# tusb8041_hub_test.net
KiCad netlist of a schematic drawn in EAGLE
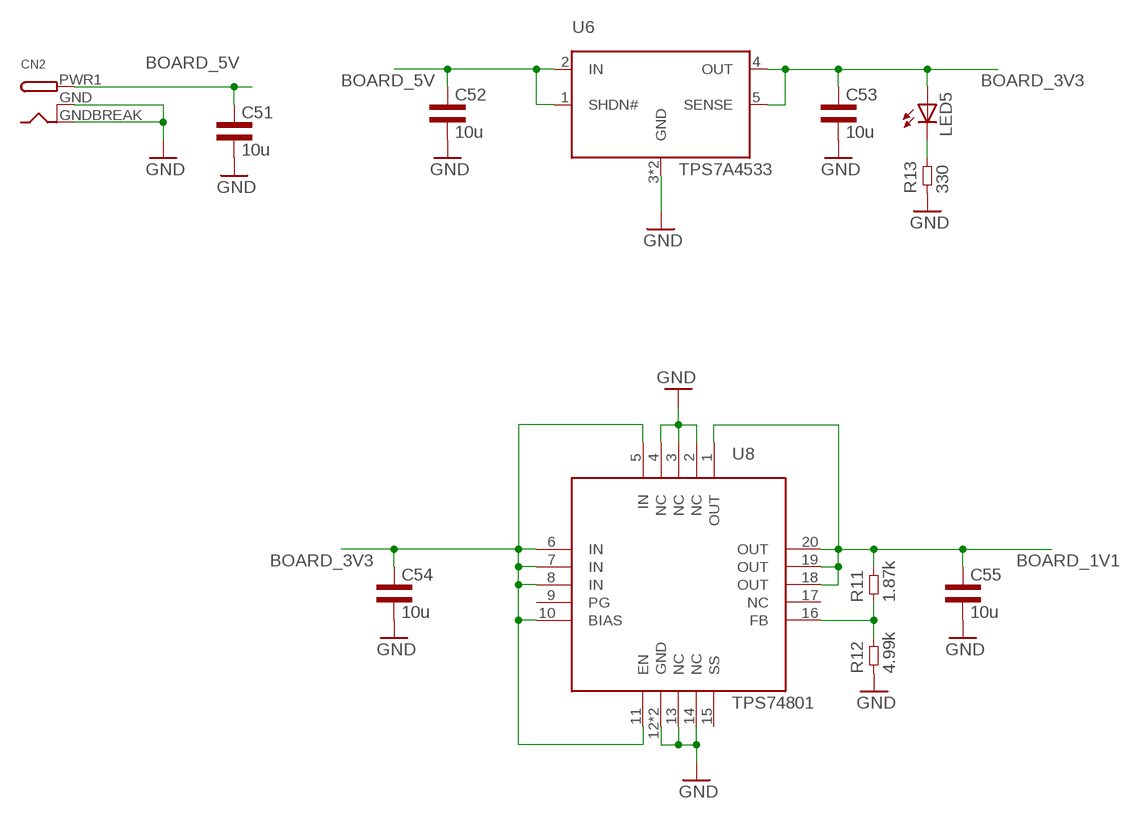
[diagram p0: schematic, sheet 1]
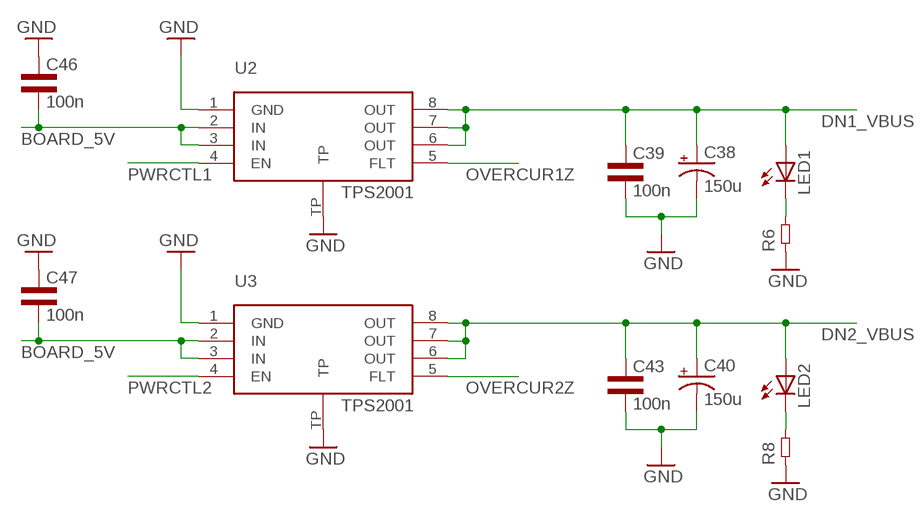
[diagram p1: schematic, sheet 2]
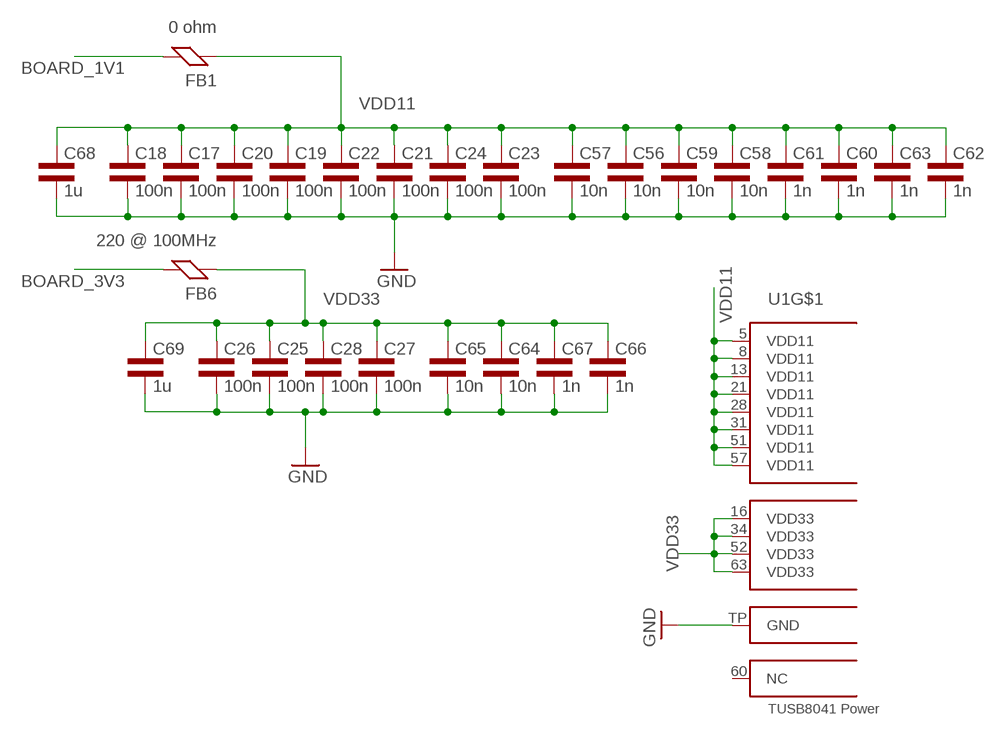
[diagram p2: schematic, sheet 3]
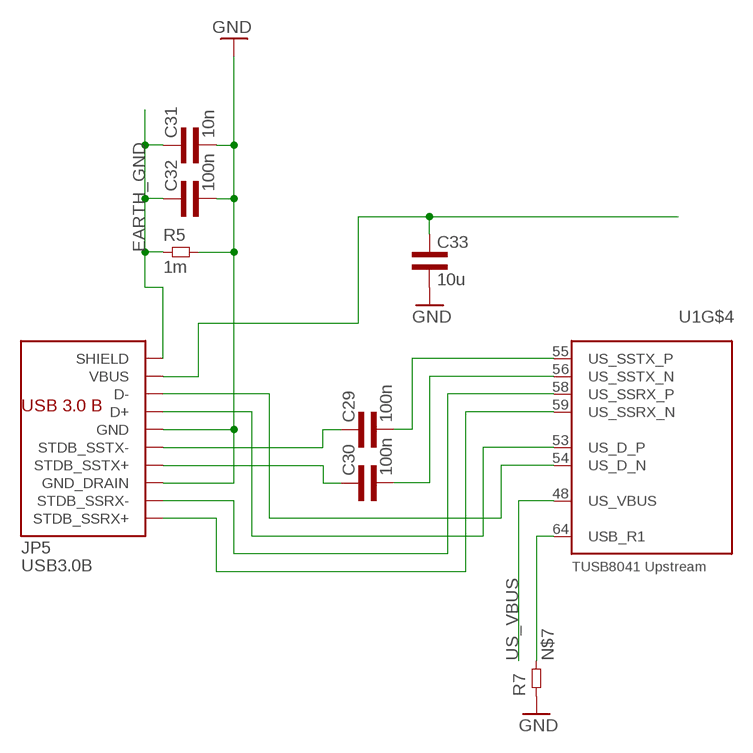
[diagram p3: schematic, sheet 4]
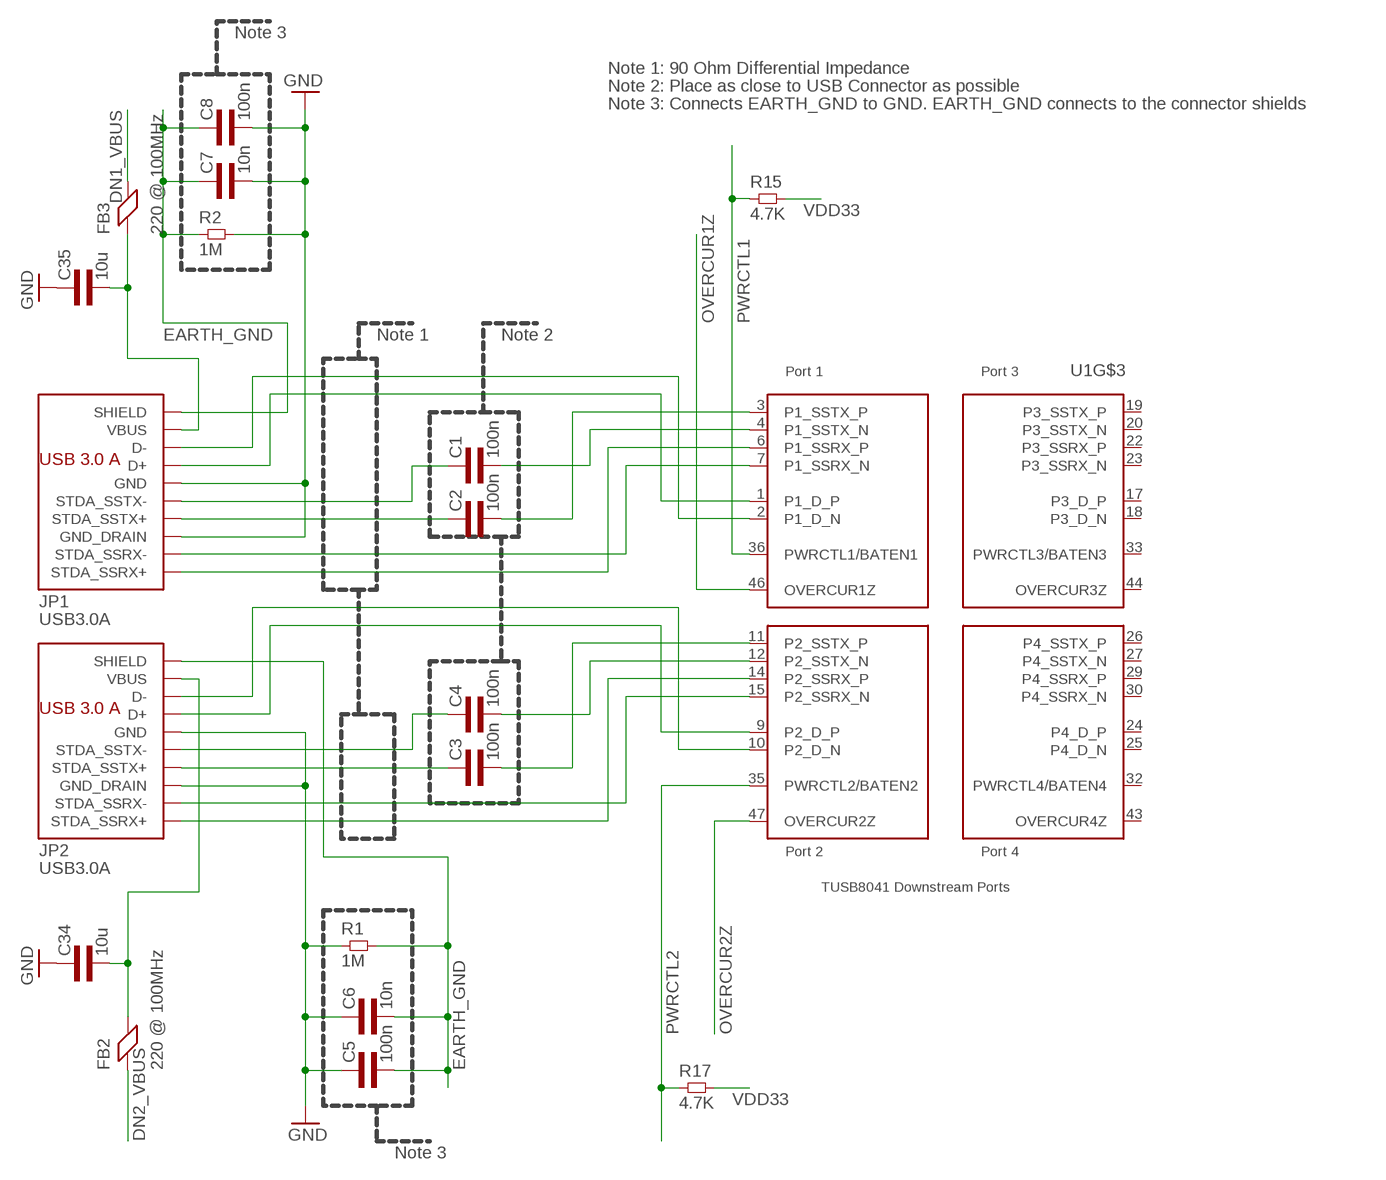
[diagram p4: schematic, sheet 5]
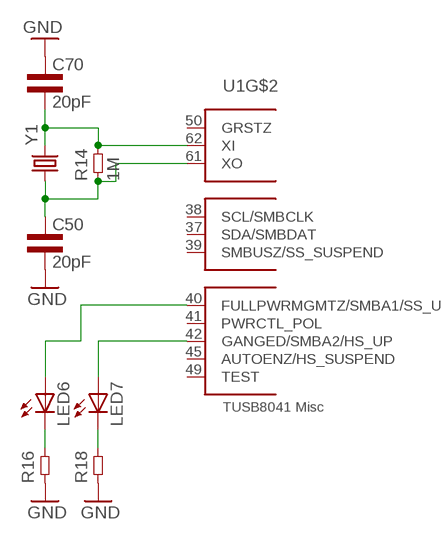
[diagram p5: schematic, sheet 6]

(export (version "E")
  (design (tool "Eeschema 10.0.6"))
  (components
    (comp (ref "C29")
      (value "100n")
      (footprint "eagle-import:0402L3")
      (libsource (lib "eagle-import") (part "CAP0402L3"))
    )
    (comp (ref "C30")
      (value "100n")
      (footprint "eagle-import:0402L3")
      (libsource (lib "eagle-import") (part "CAP0402L3"))
    )
    (comp (ref "C31")
      (value "10n")
      (footprint "eagle-import:0603L3")
      (libsource (lib "eagle-import") (part "CAP0603L3"))
    )
    (comp (ref "C32")
      (value "100n")
      (footprint "eagle-import:0603L3")
      (libsource (lib "eagle-import") (part "CAP0603L3"))
    )
    (comp (ref "C33")
      (value "10u")
      (footprint "eagle-import:1206L3")
      (libsource (lib "eagle-import") (part "CAP1206L3"))
    )
    (comp (ref "JP5")
      (value "USB3.0B")
      (footprint "eagle-import:AMPHENOLUSB3.0B")
      (libsource (lib "eagle-import") (part "USB3.0B"))
    )
    (comp (ref "R5")
      (value "1m")
      (footprint "eagle-import:0603L3")
      (libsource (lib "eagle-import") (part "RES0603L3"))
    )
    (comp (ref "R7")
      (value "RES0402L3")
      (footprint "eagle-import:0402L3")
      (libsource (lib "eagle-import") (part "RES0402L3"))
    )
    (comp (ref "U1")
      (value "TUSB8041")
      (footprint "eagle-import:VQFN64")
      (libsource (lib "eagle-import") (part "TUSB8041"))
    )
    (comp (ref "C50")
      (value "20pF")
      (footprint "eagle-import:0402L3")
      (libsource (lib "eagle-import") (part "CAP0402L3"))
    )
    (comp (ref "C70")
      (value "20pF")
      (footprint "eagle-import:0402L3")
      (libsource (lib "eagle-import") (part "CAP0402L3"))
    )
    (comp (ref "LED6")
      (value "LEDCHIPLED_0603")
      (footprint "eagle-import:CHIPLED_0603")
      (libsource (lib "eagle-import") (part "LEDCHIPLED_0603"))
    )
    (comp (ref "LED7")
      (value "LEDCHIPLED_0603")
      (footprint "eagle-import:CHIPLED_0603")
      (libsource (lib "eagle-import") (part "LEDCHIPLED_0603"))
    )
    (comp (ref "R14")
      (value "1M")
      (footprint "eagle-import:0402L3")
      (libsource (lib "eagle-import") (part "RES0402L3"))
    )
    (comp (ref "R16")
      (value "RES0402L3")
      (footprint "eagle-import:0402L3")
      (libsource (lib "eagle-import") (part "RES0402L3"))
    )
    (comp (ref "R18")
      (value "RES0402L3")
      (footprint "eagle-import:0402L3")
      (libsource (lib "eagle-import") (part "RES0402L3"))
    )
    (comp (ref "Y1")
      (value "CRYSTALHC49US")
      (footprint "eagle-import:HC49US")
      (libsource (lib "eagle-import") (part "CRYSTALHC49US"))
    )
    (comp (ref "C17")
      (value "100n")
      (footprint "eagle-import:0402L3")
      (libsource (lib "eagle-import") (part "CAP0402L3"))
    )
    (comp (ref "C18")
      (value "100n")
      (footprint "eagle-import:0402L3")
      (libsource (lib "eagle-import") (part "CAP0402L3"))
    )
    (comp (ref "C19")
      (value "100n")
      (footprint "eagle-import:0402L3")
      (libsource (lib "eagle-import") (part "CAP0402L3"))
    )
    (comp (ref "C20")
      (value "100n")
      (footprint "eagle-import:0402L3")
      (libsource (lib "eagle-import") (part "CAP0402L3"))
    )
    (comp (ref "C21")
      (value "100n")
      (footprint "eagle-import:0402L3")
      (libsource (lib "eagle-import") (part "CAP0402L3"))
    )
    (comp (ref "C22")
      (value "100n")
      (footprint "eagle-import:0402L3")
      (libsource (lib "eagle-import") (part "CAP0402L3"))
    )
    (comp (ref "C23")
      (value "100n")
      (footprint "eagle-import:0402L3")
      (libsource (lib "eagle-import") (part "CAP0402L3"))
    )
    (comp (ref "C24")
      (value "100n")
      (footprint "eagle-import:0402L3")
      (libsource (lib "eagle-import") (part "CAP0402L3"))
    )
    (comp (ref "C25")
      (value "100n")
      (footprint "eagle-import:0402L3")
      (libsource (lib "eagle-import") (part "CAP0402L3"))
    )
    (comp (ref "C26")
      (value "100n")
      (footprint "eagle-import:0402L3")
      (libsource (lib "eagle-import") (part "CAP0402L3"))
    )
    (comp (ref "C27")
      (value "100n")
      (footprint "eagle-import:0402L3")
      (libsource (lib "eagle-import") (part "CAP0402L3"))
    )
    (comp (ref "C28")
      (value "100n")
      (footprint "eagle-import:0402L3")
      (libsource (lib "eagle-import") (part "CAP0402L3"))
    )
    (comp (ref "C56")
      (value "10n")
      (footprint "eagle-import:0402L3")
      (libsource (lib "eagle-import") (part "CAP0402L3"))
    )
    (comp (ref "C57")
      (value "10n")
      (footprint "eagle-import:0402L3")
      (libsource (lib "eagle-import") (part "CAP0402L3"))
    )
    (comp (ref "C58")
      (value "10n")
      (footprint "eagle-import:0402L3")
      (libsource (lib "eagle-import") (part "CAP0402L3"))
    )
    (comp (ref "C59")
      (value "10n")
      (footprint "eagle-import:0402L3")
      (libsource (lib "eagle-import") (part "CAP0402L3"))
    )
    (comp (ref "C60")
      (value "1n")
      (footprint "eagle-import:0402L3")
      (libsource (lib "eagle-import") (part "CAP0402L3"))
    )
    (comp (ref "C61")
      (value "1n")
      (footprint "eagle-import:0402L3")
      (libsource (lib "eagle-import") (part "CAP0402L3"))
    )
    (comp (ref "C62")
      (value "1n")
      (footprint "eagle-import:0402L3")
      (libsource (lib "eagle-import") (part "CAP0402L3"))
    )
    (comp (ref "C63")
      (value "1n")
      (footprint "eagle-import:0402L3")
      (libsource (lib "eagle-import") (part "CAP0402L3"))
    )
    (comp (ref "C64")
      (value "10n")
      (footprint "eagle-import:0402L3")
      (libsource (lib "eagle-import") (part "CAP0402L3"))
    )
    (comp (ref "C65")
      (value "10n")
      (footprint "eagle-import:0402L3")
      (libsource (lib "eagle-import") (part "CAP0402L3"))
    )
    (comp (ref "C66")
      (value "1n")
      (footprint "eagle-import:0402L3")
      (libsource (lib "eagle-import") (part "CAP0402L3"))
    )
    (comp (ref "C67")
      (value "1n")
      (footprint "eagle-import:0402L3")
      (libsource (lib "eagle-import") (part "CAP0402L3"))
    )
    (comp (ref "C68")
      (value "1u")
      (footprint "eagle-import:0805L3")
      (libsource (lib "eagle-import") (part "CAP0805L3"))
    )
    (comp (ref "C69")
      (value "1u")
      (footprint "eagle-import:0805L3")
      (libsource (lib "eagle-import") (part "CAP0805L3"))
    )
    (comp (ref "FB1")
      (value "0 ohm")
      (footprint "eagle-import:0603L3")
      (libsource (lib "eagle-import") (part "FERRITE0603L3"))
    )
    (comp (ref "FB6")
      (value "220 @ 100MHz")
      (footprint "eagle-import:0603L3")
      (libsource (lib "eagle-import") (part "FERRITE0603L3"))
    )
    (comp (ref "C1")
      (value "100n")
      (footprint "eagle-import:0402L3")
      (libsource (lib "eagle-import") (part "CAP0402L3"))
    )
    (comp (ref "C2")
      (value "100n")
      (footprint "eagle-import:0402L3")
      (libsource (lib "eagle-import") (part "CAP0402L3"))
    )
    (comp (ref "C3")
      (value "100n")
      (footprint "eagle-import:0402L3")
      (libsource (lib "eagle-import") (part "CAP0402L3"))
    )
    (comp (ref "C4")
      (value "100n")
      (footprint "eagle-import:0402L3")
      (libsource (lib "eagle-import") (part "CAP0402L3"))
    )
    (comp (ref "C5")
      (value "100n")
      (footprint "eagle-import:0603L3")
      (libsource (lib "eagle-import") (part "CAP0603L3"))
    )
    (comp (ref "C6")
      (value "10n")
      (footprint "eagle-import:0603L3")
      (libsource (lib "eagle-import") (part "CAP0603L3"))
    )
    (comp (ref "C7")
      (value "10n")
      (footprint "eagle-import:0603L3")
      (libsource (lib "eagle-import") (part "CAP0603L3"))
    )
    (comp (ref "C8")
      (value "100n")
      (footprint "eagle-import:0603L3")
      (libsource (lib "eagle-import") (part "CAP0603L3"))
    )
    (comp (ref "C34")
      (value "10u")
      (footprint "eagle-import:1206L3")
      (libsource (lib "eagle-import") (part "CAP1206L3"))
    )
    (comp (ref "C35")
      (value "10u")
      (footprint "eagle-import:1206L3")
      (libsource (lib "eagle-import") (part "CAP1206L3"))
    )
    (comp (ref "FB2")
      (value "220 @ 100MHz")
      (footprint "eagle-import:0603L1")
      (libsource (lib "eagle-import") (part "FERRITE0603L1"))
    )
    (comp (ref "FB3")
      (value "220 @ 100MHz")
      (footprint "eagle-import:0603L1")
      (libsource (lib "eagle-import") (part "FERRITE0603L1"))
    )
    (comp (ref "JP1")
      (value "USB3.0A")
      (footprint "eagle-import:AMPHENOLUSB3.0A")
      (libsource (lib "eagle-import") (part "USB3.0A"))
    )
    (comp (ref "JP2")
      (value "USB3.0A")
      (footprint "eagle-import:AMPHENOLUSB3.0A")
      (libsource (lib "eagle-import") (part "USB3.0A"))
    )
    (comp (ref "R1")
      (value "1M")
      (footprint "eagle-import:0603L3")
      (libsource (lib "eagle-import") (part "RES0603L3"))
    )
    (comp (ref "R2")
      (value "1M")
      (footprint "eagle-import:0603L3")
      (libsource (lib "eagle-import") (part "RES0603L3"))
    )
    (comp (ref "R15")
      (value "4.7K")
      (footprint "eagle-import:0402L3")
      (libsource (lib "eagle-import") (part "RES0402L3"))
    )
    (comp (ref "R17")
      (value "4.7K")
      (footprint "eagle-import:0402L3")
      (libsource (lib "eagle-import") (part "RES0402L3"))
    )
    (comp (ref "C51")
      (value "10u")
      (footprint "eagle-import:1206L3")
      (libsource (lib "eagle-import") (part "CAP1206L3"))
    )
    (comp (ref "C52")
      (value "10u")
      (footprint "eagle-import:1206L3")
      (libsource (lib "eagle-import") (part "CAP1206L3"))
    )
    (comp (ref "C53")
      (value "10u")
      (footprint "eagle-import:1206L3")
      (libsource (lib "eagle-import") (part "CAP1206L3"))
    )
    (comp (ref "C54")
      (value "10u")
      (footprint "eagle-import:1206L3")
      (libsource (lib "eagle-import") (part "CAP1206L3"))
    )
    (comp (ref "C55")
      (value "10u")
      (footprint "eagle-import:1206L3")
      (libsource (lib "eagle-import") (part "CAP1206L3"))
    )
    (comp (ref "CN2")
      (value "DCBARRELSMT")
      (footprint "eagle-import:DCJACK_2MM_SMT")
      (libsource (lib "eagle-import") (part "DCBARRELSMT"))
    )
    (comp (ref "LED5")
      (value "LEDCHIP-LED0603")
      (footprint "eagle-import:CHIP-LED0603")
      (libsource (lib "eagle-import") (part "LEDCHIP-LED0603"))
    )
    (comp (ref "R11")
      (value "1.87k")
      (footprint "eagle-import:0402L3")
      (libsource (lib "eagle-import") (part "RES0402L3"))
    )
    (comp (ref "R12")
      (value "4.99k")
      (footprint "eagle-import:0402L3")
      (libsource (lib "eagle-import") (part "RES0402L3"))
    )
    (comp (ref "R13")
      (value "330")
      (footprint "eagle-import:0603L3")
      (libsource (lib "eagle-import") (part "RES0603L3"))
    )
    (comp (ref "U6")
      (value "TPS7A4533")
      (footprint "eagle-import:R-PSFM-G5")
      (libsource (lib "eagle-import") (part "TPS7A4533"))
    )
    (comp (ref "U8")
      (value "TPS74801")
      (footprint "eagle-import:S-PVQFN-N20")
      (libsource (lib "eagle-import") (part "TPS74801"))
    )
    (comp (ref "C38")
      (value "150u")
      (footprint "eagle-import:CT7343")
      (libsource (lib "eagle-import") (part "CPOL-USCT7343"))
    )
    (comp (ref "C39")
      (value "100n")
      (footprint "eagle-import:0603L3")
      (libsource (lib "eagle-import") (part "CAP0603L3"))
    )
    (comp (ref "C40")
      (value "150u")
      (footprint "eagle-import:CT7343")
      (libsource (lib "eagle-import") (part "CPOL-USCT7343"))
    )
    (comp (ref "C43")
      (value "100n")
      (footprint "eagle-import:0603L3")
      (libsource (lib "eagle-import") (part "CAP0603L3"))
    )
    (comp (ref "C46")
      (value "100n")
      (footprint "eagle-import:0603L3")
      (libsource (lib "eagle-import") (part "CAP0603L3"))
    )
    (comp (ref "C47")
      (value "100n")
      (footprint "eagle-import:0603L3")
      (libsource (lib "eagle-import") (part "CAP0603L3"))
    )
    (comp (ref "LED1")
      (value "LEDCHIP-LED0603")
      (footprint "eagle-import:CHIP-LED0603")
      (libsource (lib "eagle-import") (part "LEDCHIP-LED0603"))
    )
    (comp (ref "LED2")
      (value "LEDCHIP-LED0603")
      (footprint "eagle-import:CHIP-LED0603")
      (libsource (lib "eagle-import") (part "LEDCHIP-LED0603"))
    )
    (comp (ref "R6")
      (value "RES0603L3")
      (footprint "eagle-import:0603L3")
      (libsource (lib "eagle-import") (part "RES0603L3"))
    )
    (comp (ref "R8")
      (value "RES0603L3")
      (footprint "eagle-import:0603L3")
      (libsource (lib "eagle-import") (part "RES0603L3"))
    )
    (comp (ref "U2")
      (value "TPS2001")
      (footprint "eagle-import:S-PDSO-G8")
      (libsource (lib "eagle-import") (part "TPS2001"))
    )
    (comp (ref "U3")
      (value "TPS2001")
      (footprint "eagle-import:S-PDSO-G8")
      (libsource (lib "eagle-import") (part "TPS2001"))
    )
  )
  (nets
    (net (code "1") (name "BOARD_1V1") (class "Default")
      (node (ref "C55") (pin "1") (pinfunction "1_1") (pintype "bidirectional"))
      (node (ref "FB1") (pin "P$2") (pinfunction "2_P$2") (pintype "bidirectional"))
      (node (ref "R11") (pin "P$2") (pinfunction "2_P$2") (pintype "bidirectional"))
      (node (ref "U8") (pin "1") (pinfunction "OUT_1") (pintype "bidirectional"))
      (node (ref "U8") (pin "18") (pinfunction "OUT_18") (pintype "bidirectional"))
      (node (ref "U8") (pin "19") (pinfunction "OUT_19") (pintype "bidirectional"))
      (node (ref "U8") (pin "20") (pinfunction "OUT_20") (pintype "bidirectional"))
    )
    (net (code "2") (name "BOARD_3V3") (class "Default")
      (node (ref "C53") (pin "1") (pinfunction "1_1") (pintype "bidirectional"))
      (node (ref "C54") (pin "1") (pinfunction "1_1") (pintype "bidirectional"))
      (node (ref "FB6") (pin "P$2") (pinfunction "2_P$2") (pintype "bidirectional"))
      (node (ref "LED5") (pin "A") (pinfunction "A_A") (pintype "passive"))
      (node (ref "U6") (pin "4") (pinfunction "OUT_4") (pintype "bidirectional"))
      (node (ref "U6") (pin "5") (pinfunction "SENSE_5") (pintype "bidirectional"))
      (node (ref "U8") (pin "10") (pinfunction "BIAS_10") (pintype "bidirectional"))
      (node (ref "U8") (pin "11") (pinfunction "EN_11") (pintype "bidirectional"))
      (node (ref "U8") (pin "5") (pinfunction "IN_5") (pintype "bidirectional"))
      (node (ref "U8") (pin "6") (pinfunction "IN_6") (pintype "bidirectional"))
      (node (ref "U8") (pin "7") (pinfunction "IN_7") (pintype "bidirectional"))
      (node (ref "U8") (pin "8") (pinfunction "IN_8") (pintype "bidirectional"))
    )
    (net (code "3") (name "BOARD_5V") (class "Default")
      (node (ref "C46") (pin "P$2") (pinfunction "2_P$2") (pintype "bidirectional"))
      (node (ref "C47") (pin "P$2") (pinfunction "2_P$2") (pintype "bidirectional"))
      (node (ref "C51") (pin "1") (pinfunction "1_1") (pintype "bidirectional"))
      (node (ref "C52") (pin "1") (pinfunction "1_1") (pintype "bidirectional"))
      (node (ref "CN2") (pin "PWR1") (pinfunction "PWR_PWR1") (pintype "power_in"))
      (node (ref "U2") (pin "2") (pinfunction "IN_2") (pintype "bidirectional"))
      (node (ref "U2") (pin "3") (pinfunction "IN_3") (pintype "bidirectional"))
      (node (ref "U3") (pin "2") (pinfunction "IN_2") (pintype "bidirectional"))
      (node (ref "U3") (pin "3") (pinfunction "IN_3") (pintype "bidirectional"))
      (node (ref "U6") (pin "1") (pinfunction "SHDN#_1") (pintype "bidirectional"))
      (node (ref "U6") (pin "2") (pinfunction "IN_2") (pintype "bidirectional"))
    )
    (net (code "4") (name "DN1_VBUS") (class "Default")
      (node (ref "C38") (pin "+") (pinfunction "+_+") (pintype "passive"))
      (node (ref "C39") (pin "P$1") (pinfunction "1_P$1") (pintype "bidirectional"))
      (node (ref "FB3") (pin "2") (pinfunction "2_2") (pintype "bidirectional"))
      (node (ref "LED1") (pin "A") (pinfunction "A_A") (pintype "passive"))
      (node (ref "U2") (pin "6") (pinfunction "OUT_6") (pintype "bidirectional"))
      (node (ref "U2") (pin "7") (pinfunction "OUT_7") (pintype "bidirectional"))
      (node (ref "U2") (pin "8") (pinfunction "OUT_8") (pintype "bidirectional"))
    )
    (net (code "5") (name "DN2_VBUS") (class "Default")
      (node (ref "C40") (pin "+") (pinfunction "+_+") (pintype "passive"))
      (node (ref "C43") (pin "P$1") (pinfunction "1_P$1") (pintype "bidirectional"))
      (node (ref "FB2") (pin "1") (pinfunction "1_1") (pintype "bidirectional"))
      (node (ref "LED2") (pin "A") (pinfunction "A_A") (pintype "passive"))
      (node (ref "U3") (pin "6") (pinfunction "OUT_6") (pintype "bidirectional"))
      (node (ref "U3") (pin "7") (pinfunction "OUT_7") (pintype "bidirectional"))
      (node (ref "U3") (pin "8") (pinfunction "OUT_8") (pintype "bidirectional"))
    )
    (net (code "6") (name "EARTH_GND") (class "Default")
      (node (ref "C31") (pin "P$1") (pinfunction "1_P$1") (pintype "bidirectional"))
      (node (ref "C32") (pin "P$1") (pinfunction "1_P$1") (pintype "bidirectional"))
      (node (ref "C5") (pin "P$2") (pinfunction "2_P$2") (pintype "bidirectional"))
      (node (ref "C6") (pin "P$2") (pinfunction "2_P$2") (pintype "bidirectional"))
      (node (ref "C7") (pin "P$1") (pinfunction "1_P$1") (pintype "bidirectional"))
      (node (ref "C8") (pin "P$1") (pinfunction "1_P$1") (pintype "bidirectional"))
      (node (ref "JP1") (pin "10@1") (pinfunction "SHIELD_10@1") (pintype "bidirectional"))
      (node (ref "JP1") (pin "10@2") (pinfunction "SHIELD_10@2") (pintype "bidirectional"))
      (node (ref "JP2") (pin "10@1") (pinfunction "SHIELD_10@1") (pintype "bidirectional"))
      (node (ref "JP2") (pin "10@2") (pinfunction "SHIELD_10@2") (pintype "bidirectional"))
      (node (ref "JP5") (pin "10@1") (pinfunction "SHIELD_10@1") (pintype "bidirectional"))
      (node (ref "JP5") (pin "10@2") (pinfunction "SHIELD_10@2") (pintype "bidirectional"))
      (node (ref "R1") (pin "P$2") (pinfunction "2_P$2") (pintype "bidirectional"))
      (node (ref "R2") (pin "P$1") (pinfunction "1_P$1") (pintype "bidirectional"))
      (node (ref "R5") (pin "P$1") (pinfunction "1_P$1") (pintype "bidirectional"))
    )
    (net (code "7") (name "GND") (class "Default")
      (node (ref "C17") (pin "P$2") (pinfunction "2_P$2") (pintype "bidirectional"))
      (node (ref "C18") (pin "P$2") (pinfunction "2_P$2") (pintype "bidirectional"))
      (node (ref "C19") (pin "P$2") (pinfunction "2_P$2") (pintype "bidirectional"))
      (node (ref "C20") (pin "P$2") (pinfunction "2_P$2") (pintype "bidirectional"))
      (node (ref "C21") (pin "P$2") (pinfunction "2_P$2") (pintype "bidirectional"))
      (node (ref "C22") (pin "P$2") (pinfunction "2_P$2") (pintype "bidirectional"))
      (node (ref "C23") (pin "P$2") (pinfunction "2_P$2") (pintype "bidirectional"))
      (node (ref "C24") (pin "P$2") (pinfunction "2_P$2") (pintype "bidirectional"))
      (node (ref "C25") (pin "P$2") (pinfunction "2_P$2") (pintype "bidirectional"))
      (node (ref "C26") (pin "P$2") (pinfunction "2_P$2") (pintype "bidirectional"))
      (node (ref "C27") (pin "P$2") (pinfunction "2_P$2") (pintype "bidirectional"))
      (node (ref "C28") (pin "P$2") (pinfunction "2_P$2") (pintype "bidirectional"))
      (node (ref "C31") (pin "P$2") (pinfunction "2_P$2") (pintype "bidirectional"))
      (node (ref "C32") (pin "P$2") (pinfunction "2_P$2") (pintype "bidirectional"))
      (node (ref "C33") (pin "2") (pinfunction "2_2") (pintype "bidirectional"))
      (node (ref "C34") (pin "1") (pinfunction "1_1") (pintype "bidirectional"))
      (node (ref "C35") (pin "1") (pinfunction "1_1") (pintype "bidirectional"))
      (node (ref "C38") (pin "-") (pinfunction "-_-") (pintype "passive"))
      (node (ref "C39") (pin "P$2") (pinfunction "2_P$2") (pintype "bidirectional"))
      (node (ref "C40") (pin "-") (pinfunction "-_-") (pintype "passive"))
      (node (ref "C43") (pin "P$2") (pinfunction "2_P$2") (pintype "bidirectional"))
      (node (ref "C46") (pin "P$1") (pinfunction "1_P$1") (pintype "bidirectional"))
      (node (ref "C47") (pin "P$1") (pinfunction "1_P$1") (pintype "bidirectional"))
      (node (ref "C5") (pin "P$1") (pinfunction "1_P$1") (pintype "bidirectional"))
      (node (ref "C50") (pin "P$2") (pinfunction "2_P$2") (pintype "bidirectional"))
      (node (ref "C51") (pin "2") (pinfunction "2_2") (pintype "bidirectional"))
      (node (ref "C52") (pin "2") (pinfunction "2_2") (pintype "bidirectional"))
      (node (ref "C53") (pin "2") (pinfunction "2_2") (pintype "bidirectional"))
      (node (ref "C54") (pin "2") (pinfunction "2_2") (pintype "bidirectional"))
      (node (ref "C55") (pin "2") (pinfunction "2_2") (pintype "bidirectional"))
      (node (ref "C56") (pin "P$2") (pinfunction "2_P$2") (pintype "bidirectional"))
      (node (ref "C57") (pin "P$2") (pinfunction "2_P$2") (pintype "bidirectional"))
      (node (ref "C58") (pin "P$2") (pinfunction "2_P$2") (pintype "bidirectional"))
      (node (ref "C59") (pin "P$2") (pinfunction "2_P$2") (pintype "bidirectional"))
      (node (ref "C6") (pin "P$1") (pinfunction "1_P$1") (pintype "bidirectional"))
      (node (ref "C60") (pin "P$2") (pinfunction "2_P$2") (pintype "bidirectional"))
      (node (ref "C61") (pin "P$2") (pinfunction "2_P$2") (pintype "bidirectional"))
      (node (ref "C62") (pin "P$2") (pinfunction "2_P$2") (pintype "bidirectional"))
      (node (ref "C63") (pin "P$2") (pinfunction "2_P$2") (pintype "bidirectional"))
      (node (ref "C64") (pin "P$2") (pinfunction "2_P$2") (pintype "bidirectional"))
      (node (ref "C65") (pin "P$2") (pinfunction "2_P$2") (pintype "bidirectional"))
      (node (ref "C66") (pin "P$2") (pinfunction "2_P$2") (pintype "bidirectional"))
      (node (ref "C67") (pin "P$2") (pinfunction "2_P$2") (pintype "bidirectional"))
      (node (ref "C68") (pin "2") (pinfunction "2_2") (pintype "bidirectional"))
      (node (ref "C69") (pin "2") (pinfunction "2_2") (pintype "bidirectional"))
      (node (ref "C7") (pin "P$2") (pinfunction "2_P$2") (pintype "bidirectional"))
      (node (ref "C70") (pin "P$1") (pinfunction "1_P$1") (pintype "bidirectional"))
      (node (ref "C8") (pin "P$2") (pinfunction "2_P$2") (pintype "bidirectional"))
      (node (ref "CN2") (pin "GND") (pinfunction "GNDBREAK_GND") (pintype "power_in"))
      (node (ref "CN2") (pin "GNDBREAK") (pinfunction "GND_GNDBREAK") (pintype "power_in"))
      (node (ref "JP1") (pin "4") (pinfunction "GND_4") (pintype "bidirectional"))
      (node (ref "JP1") (pin "7") (pinfunction "GND_DRAIN_7") (pintype "bidirectional"))
      (node (ref "JP2") (pin "4") (pinfunction "GND_4") (pintype "bidirectional"))
      (node (ref "JP2") (pin "7") (pinfunction "GND_DRAIN_7") (pintype "bidirectional"))
      (node (ref "JP5") (pin "4") (pinfunction "GND_4") (pintype "bidirectional"))
      (node (ref "JP5") (pin "7") (pinfunction "GND_DRAIN_7") (pintype "bidirectional"))
      (node (ref "R1") (pin "P$1") (pinfunction "1_P$1") (pintype "bidirectional"))
      (node (ref "R12") (pin "P$1") (pinfunction "1_P$1") (pintype "bidirectional"))
      (node (ref "R13") (pin "P$1") (pinfunction "1_P$1") (pintype "bidirectional"))
      (node (ref "R16") (pin "P$1") (pinfunction "1_P$1") (pintype "bidirectional"))
      (node (ref "R18") (pin "P$1") (pinfunction "1_P$1") (pintype "bidirectional"))
      (node (ref "R2") (pin "P$2") (pinfunction "2_P$2") (pintype "bidirectional"))
      (node (ref "R5") (pin "P$2") (pinfunction "2_P$2") (pintype "bidirectional"))
      (node (ref "R6") (pin "P$1") (pinfunction "1_P$1") (pintype "bidirectional"))
      (node (ref "R7") (pin "P$1") (pinfunction "1_P$1") (pintype "bidirectional"))
      (node (ref "R8") (pin "P$1") (pinfunction "1_P$1") (pintype "bidirectional"))
      (node (ref "U1") (pin "TP") (pinfunction "GND_TP") (pintype "bidirectional"))
      (node (ref "U2") (pin "1") (pinfunction "GND_1") (pintype "bidirectional"))
      (node (ref "U2") (pin "TP") (pinfunction "TP_TP") (pintype "bidirectional"))
      (node (ref "U3") (pin "1") (pinfunction "GND_1") (pintype "bidirectional"))
      (node (ref "U3") (pin "TP") (pinfunction "TP_TP") (pintype "bidirectional"))
      (node (ref "U6") (pin "3") (pinfunction "GND_3") (pintype "bidirectional"))
      (node (ref "U6") (pin "TP") (pinfunction "GND_TP") (pintype "bidirectional"))
      (node (ref "U8") (pin "12") (pinfunction "GND_12") (pintype "bidirectional"))
      (node (ref "U8") (pin "13") (pinfunction "NC_13") (pintype "bidirectional"))
      (node (ref "U8") (pin "14") (pinfunction "NC_14") (pintype "bidirectional"))
      (node (ref "U8") (pin "2") (pinfunction "NC_2") (pintype "bidirectional"))
      (node (ref "U8") (pin "3") (pinfunction "NC_3") (pintype "bidirectional"))
      (node (ref "U8") (pin "4") (pinfunction "NC_4") (pintype "bidirectional"))
      (node (ref "U8") (pin "TP") (pinfunction "GND_TP") (pintype "bidirectional"))
    )
    (net (code "8") (name "N$7") (class "Default")
      (node (ref "R7") (pin "P$2") (pinfunction "2_P$2") (pintype "bidirectional"))
      (node (ref "U1") (pin "64") (pinfunction "USB_R1_64") (pintype "bidirectional"))
    )
    (net (code "9") (name "Net-(C1-1)") (class "Default")
      (node (ref "C1") (pin "P$1") (pinfunction "1_P$1") (pintype "bidirectional"))
      (node (ref "JP1") (pin "8") (pinfunction "STDA_SSTX-_8") (pintype "bidirectional"))
    )
    (net (code "10") (name "Net-(C1-2)") (class "Default")
      (node (ref "C1") (pin "P$2") (pinfunction "2_P$2") (pintype "bidirectional"))
      (node (ref "U1") (pin "4") (pinfunction "P1_SSTX_N_4") (pintype "bidirectional"))
    )
    (net (code "11") (name "Net-(C2-1)") (class "Default")
      (node (ref "C2") (pin "P$1") (pinfunction "1_P$1") (pintype "bidirectional"))
      (node (ref "JP1") (pin "9") (pinfunction "STDA_SSTX+_9") (pintype "bidirectional"))
    )
    (net (code "12") (name "Net-(C2-2)") (class "Default")
      (node (ref "C2") (pin "P$2") (pinfunction "2_P$2") (pintype "bidirectional"))
      (node (ref "U1") (pin "3") (pinfunction "P1_SSTX_P_3") (pintype "bidirectional"))
    )
    (net (code "13") (name "Net-(C3-1)") (class "Default")
      (node (ref "C3") (pin "P$1") (pinfunction "1_P$1") (pintype "bidirectional"))
      (node (ref "JP2") (pin "9") (pinfunction "STDA_SSTX+_9") (pintype "bidirectional"))
    )
    (net (code "14") (name "Net-(C3-2)") (class "Default")
      (node (ref "C3") (pin "P$2") (pinfunction "2_P$2") (pintype "bidirectional"))
      (node (ref "U1") (pin "11") (pinfunction "P2_SSTX_P_11") (pintype "bidirectional"))
    )
    (net (code "15") (name "Net-(C4-1)") (class "Default")
      (node (ref "C4") (pin "P$1") (pinfunction "1_P$1") (pintype "bidirectional"))
      (node (ref "JP2") (pin "8") (pinfunction "STDA_SSTX-_8") (pintype "bidirectional"))
    )
    (net (code "16") (name "Net-(C4-2)") (class "Default")
      (node (ref "C4") (pin "P$2") (pinfunction "2_P$2") (pintype "bidirectional"))
      (node (ref "U1") (pin "12") (pinfunction "P2_SSTX_N_12") (pintype "bidirectional"))
    )
    (net (code "17") (name "Net-(C29-1)") (class "Default")
      (node (ref "C29") (pin "P$1") (pinfunction "1_P$1") (pintype "bidirectional"))
      (node (ref "JP5") (pin "5") (pinfunction "STDB_SSTX-_5") (pintype "bidirectional"))
    )
    (net (code "18") (name "Net-(C29-2)") (class "Default")
      (node (ref "C29") (pin "P$2") (pinfunction "2_P$2") (pintype "bidirectional"))
      (node (ref "U1") (pin "55") (pinfunction "US_SSTX_P_55") (pintype "bidirectional"))
    )
    (net (code "19") (name "Net-(C30-1)") (class "Default")
      (node (ref "C30") (pin "P$1") (pinfunction "1_P$1") (pintype "bidirectional"))
      (node (ref "JP5") (pin "6") (pinfunction "STDB_SSTX+_6") (pintype "bidirectional"))
    )
    (net (code "20") (name "Net-(C30-2)") (class "Default")
      (node (ref "C30") (pin "P$2") (pinfunction "2_P$2") (pintype "bidirectional"))
      (node (ref "U1") (pin "56") (pinfunction "US_SSTX_N_56") (pintype "bidirectional"))
    )
    (net (code "21") (name "Net-(C50-1)") (class "Default")
      (node (ref "C50") (pin "P$1") (pinfunction "1_P$1") (pintype "bidirectional"))
      (node (ref "R14") (pin "P$1") (pinfunction "1_P$1") (pintype "bidirectional"))
      (node (ref "U1") (pin "61") (pinfunction "XO_61") (pintype "bidirectional"))
      (node (ref "Y1") (pin "1") (pinfunction "1_1") (pintype "passive"))
    )
    (net (code "22") (name "Net-(C70-2)") (class "Default")
      (node (ref "C70") (pin "P$2") (pinfunction "2_P$2") (pintype "bidirectional"))
      (node (ref "R14") (pin "P$2") (pinfunction "2_P$2") (pintype "bidirectional"))
      (node (ref "U1") (pin "62") (pinfunction "XI_62") (pintype "bidirectional"))
      (node (ref "Y1") (pin "2") (pinfunction "2_2") (pintype "passive"))
    )
    (net (code "23") (name "Net-(JP1-D+)") (class "Default")
      (node (ref "JP1") (pin "3") (pinfunction "D+_3") (pintype "bidirectional"))
      (node (ref "U1") (pin "1") (pinfunction "P1_D_P_1") (pintype "bidirectional"))
    )
    (net (code "24") (name "Net-(JP1-D-)") (class "Default")
      (node (ref "JP1") (pin "2") (pinfunction "D-_2") (pintype "bidirectional"))
      (node (ref "U1") (pin "2") (pinfunction "P1_D_N_2") (pintype "bidirectional"))
    )
    (net (code "25") (name "Net-(JP1-STDA_SSRX+)") (class "Default")
      (node (ref "JP1") (pin "6") (pinfunction "STDA_SSRX+_6") (pintype "bidirectional"))
      (node (ref "U1") (pin "6") (pinfunction "P1_SSRX_P_6") (pintype "bidirectional"))
    )
    (net (code "26") (name "Net-(JP1-STDA_SSRX-)") (class "Default")
      (node (ref "JP1") (pin "5") (pinfunction "STDA_SSRX-_5") (pintype "bidirectional"))
      (node (ref "U1") (pin "7") (pinfunction "P1_SSRX_N_7") (pintype "bidirectional"))
    )
    (net (code "27") (name "Net-(JP1-VBUS)") (class "Default")
      (node (ref "C35") (pin "2") (pinfunction "2_2") (pintype "bidirectional"))
      (node (ref "FB3") (pin "1") (pinfunction "1_1") (pintype "bidirectional"))
      (node (ref "JP1") (pin "1") (pinfunction "VBUS_1") (pintype "bidirectional"))
    )
    (net (code "28") (name "Net-(JP2-D+)") (class "Default")
      (node (ref "JP2") (pin "3") (pinfunction "D+_3") (pintype "bidirectional"))
      (node (ref "U1") (pin "9") (pinfunction "P2_D_P_9") (pintype "bidirectional"))
    )
    (net (code "29") (name "Net-(JP2-D-)") (class "Default")
      (node (ref "JP2") (pin "2") (pinfunction "D-_2") (pintype "bidirectional"))
      (node (ref "U1") (pin "10") (pinfunction "P2_D_N_10") (pintype "bidirectional"))
    )
    (net (code "30") (name "Net-(JP2-STDA_SSRX+)") (class "Default")
      (node (ref "JP2") (pin "6") (pinfunction "STDA_SSRX+_6") (pintype "bidirectional"))
      (node (ref "U1") (pin "14") (pinfunction "P2_SSRX_P_14") (pintype "bidirectional"))
    )
    (net (code "31") (name "Net-(JP2-STDA_SSRX-)") (class "Default")
      (node (ref "JP2") (pin "5") (pinfunction "STDA_SSRX-_5") (pintype "bidirectional"))
      (node (ref "U1") (pin "15") (pinfunction "P2_SSRX_N_15") (pintype "bidirectional"))
    )
    (net (code "32") (name "Net-(JP2-VBUS)") (class "Default")
      (node (ref "C34") (pin "2") (pinfunction "2_2") (pintype "bidirectional"))
      (node (ref "FB2") (pin "2") (pinfunction "2_2") (pintype "bidirectional"))
      (node (ref "JP2") (pin "1") (pinfunction "VBUS_1") (pintype "bidirectional"))
    )
    (net (code "33") (name "Net-(JP5-D+)") (class "Default")
      (node (ref "JP5") (pin "3") (pinfunction "D+_3") (pintype "bidirectional"))
      (node (ref "U1") (pin "53") (pinfunction "US_D_P_53") (pintype "bidirectional"))
    )
    (net (code "34") (name "Net-(JP5-D-)") (class "Default")
      (node (ref "JP5") (pin "2") (pinfunction "D-_2") (pintype "bidirectional"))
      (node (ref "U1") (pin "54") (pinfunction "US_D_N_54") (pintype "bidirectional"))
    )
    (net (code "35") (name "Net-(JP5-STDB_SSRX+)") (class "Default")
      (node (ref "JP5") (pin "9") (pinfunction "STDB_SSRX+_9") (pintype "bidirectional"))
      (node (ref "U1") (pin "59") (pinfunction "US_SSRX_N_59") (pintype "bidirectional"))
    )
    (net (code "36") (name "Net-(JP5-STDB_SSRX-)") (class "Default")
      (node (ref "JP5") (pin "8") (pinfunction "STDB_SSRX-_8") (pintype "bidirectional"))
      (node (ref "U1") (pin "58") (pinfunction "US_SSRX_P_58") (pintype "bidirectional"))
    )
    (net (code "37") (name "Net-(R6-2)") (class "Default")
      (node (ref "LED1") (pin "C") (pinfunction "C_C") (pintype "passive"))
      (node (ref "R6") (pin "P$2") (pinfunction "2_P$2") (pintype "bidirectional"))
    )
    (net (code "38") (name "Net-(R8-2)") (class "Default")
      (node (ref "LED2") (pin "C") (pinfunction "C_C") (pintype "passive"))
      (node (ref "R8") (pin "P$2") (pinfunction "2_P$2") (pintype "bidirectional"))
    )
    (net (code "39") (name "Net-(R11-1)") (class "Default")
      (node (ref "R11") (pin "P$1") (pinfunction "1_P$1") (pintype "bidirectional"))
      (node (ref "R12") (pin "P$2") (pinfunction "2_P$2") (pintype "bidirectional"))
      (node (ref "U8") (pin "16") (pinfunction "FB_16") (pintype "bidirectional"))
    )
    (net (code "40") (name "Net-(R13-2)") (class "Default")
      (node (ref "LED5") (pin "C") (pinfunction "C_C") (pintype "passive"))
      (node (ref "R13") (pin "P$2") (pinfunction "2_P$2") (pintype "bidirectional"))
    )
    (net (code "41") (name "Net-(R16-2)") (class "Default")
      (node (ref "LED6") (pin "C") (pinfunction "C_C") (pintype "passive"))
      (node (ref "R16") (pin "P$2") (pinfunction "2_P$2") (pintype "bidirectional"))
    )
    (net (code "42") (name "Net-(R18-2)") (class "Default")
      (node (ref "LED7") (pin "C") (pinfunction "C_C") (pintype "passive"))
      (node (ref "R18") (pin "P$2") (pinfunction "2_P$2") (pintype "bidirectional"))
    )
    (net (code "43") (name "Net-(U1B-FULLPWRMGMTZ{slash}SMBA1{slash}SS_UP)") (class "Default")
      (node (ref "LED6") (pin "A") (pinfunction "A_A") (pintype "passive"))
      (node (ref "U1") (pin "40") (pinfunction "FULLPWRMGMTZ/SMBA1/SS_UP_40") (pintype "bidirectional"))
    )
    (net (code "44") (name "Net-(U1B-GANGED{slash}SMBA2{slash}HS_UP)") (class "Default")
      (node (ref "LED7") (pin "A") (pinfunction "A_A") (pintype "passive"))
      (node (ref "U1") (pin "42") (pinfunction "GANGED/SMBA2/HS_UP_42") (pintype "bidirectional"))
    )
    (net (code "45") (name "OVERCUR1Z") (class "Default")
      (node (ref "U1") (pin "46") (pinfunction "OVERCUR1Z_46") (pintype "bidirectional"))
      (node (ref "U2") (pin "5") (pinfunction "FLT_5") (pintype "bidirectional"))
    )
    (net (code "46") (name "OVERCUR2Z") (class "Default")
      (node (ref "U1") (pin "47") (pinfunction "OVERCUR2Z_47") (pintype "bidirectional"))
      (node (ref "U3") (pin "5") (pinfunction "FLT_5") (pintype "bidirectional"))
    )
    (net (code "47") (name "PWRCTL1") (class "Default")
      (node (ref "R15") (pin "P$1") (pinfunction "1_P$1") (pintype "bidirectional"))
      (node (ref "U1") (pin "36") (pinfunction "PWRCTL1/BATEN1_36") (pintype "bidirectional"))
      (node (ref "U2") (pin "4") (pinfunction "EN_4") (pintype "bidirectional"))
    )
    (net (code "48") (name "PWRCTL2") (class "Default")
      (node (ref "R17") (pin "P$1") (pinfunction "1_P$1") (pintype "bidirectional"))
      (node (ref "U1") (pin "35") (pinfunction "PWRCTL2/BATEN2_35") (pintype "bidirectional"))
      (node (ref "U3") (pin "4") (pinfunction "EN_4") (pintype "bidirectional"))
    )
    (net (code "49") (name "US_VBUS") (class "Default")
      (node (ref "C33") (pin "1") (pinfunction "1_1") (pintype "bidirectional"))
      (node (ref "JP5") (pin "1") (pinfunction "VBUS_1") (pintype "bidirectional"))
      (node (ref "U1") (pin "48") (pinfunction "US_VBUS_48") (pintype "bidirectional"))
    )
    (net (code "50") (name "VDD11") (class "Default")
      (node (ref "C17") (pin "P$1") (pinfunction "1_P$1") (pintype "bidirectional"))
      (node (ref "C18") (pin "P$1") (pinfunction "1_P$1") (pintype "bidirectional"))
      (node (ref "C19") (pin "P$1") (pinfunction "1_P$1") (pintype "bidirectional"))
      (node (ref "C20") (pin "P$1") (pinfunction "1_P$1") (pintype "bidirectional"))
      (node (ref "C21") (pin "P$1") (pinfunction "1_P$1") (pintype "bidirectional"))
      (node (ref "C22") (pin "P$1") (pinfunction "1_P$1") (pintype "bidirectional"))
      (node (ref "C23") (pin "P$1") (pinfunction "1_P$1") (pintype "bidirectional"))
      (node (ref "C24") (pin "P$1") (pinfunction "1_P$1") (pintype "bidirectional"))
      (node (ref "C56") (pin "P$1") (pinfunction "1_P$1") (pintype "bidirectional"))
      (node (ref "C57") (pin "P$1") (pinfunction "1_P$1") (pintype "bidirectional"))
      (node (ref "C58") (pin "P$1") (pinfunction "1_P$1") (pintype "bidirectional"))
      (node (ref "C59") (pin "P$1") (pinfunction "1_P$1") (pintype "bidirectional"))
      (node (ref "C60") (pin "P$1") (pinfunction "1_P$1") (pintype "bidirectional"))
      (node (ref "C61") (pin "P$1") (pinfunction "1_P$1") (pintype "bidirectional"))
      (node (ref "C62") (pin "P$1") (pinfunction "1_P$1") (pintype "bidirectional"))
      (node (ref "C63") (pin "P$1") (pinfunction "1_P$1") (pintype "bidirectional"))
      (node (ref "C68") (pin "1") (pinfunction "1_1") (pintype "bidirectional"))
      (node (ref "FB1") (pin "P$1") (pinfunction "1_P$1") (pintype "bidirectional"))
      (node (ref "U1") (pin "13") (pinfunction "VDD11_13") (pintype "bidirectional"))
      (node (ref "U1") (pin "21") (pinfunction "VDD11_21") (pintype "bidirectional"))
      (node (ref "U1") (pin "28") (pinfunction "VDD11_28") (pintype "bidirectional"))
      (node (ref "U1") (pin "31") (pinfunction "VDD11_31") (pintype "bidirectional"))
      (node (ref "U1") (pin "5") (pinfunction "VDD11_5") (pintype "bidirectional"))
      (node (ref "U1") (pin "51") (pinfunction "VDD11_51") (pintype "bidirectional"))
      (node (ref "U1") (pin "57") (pinfunction "VDD11_57") (pintype "bidirectional"))
      (node (ref "U1") (pin "8") (pinfunction "VDD11_8") (pintype "bidirectional"))
    )
    (net (code "51") (name "VDD33") (class "Default")
      (node (ref "C25") (pin "P$1") (pinfunction "1_P$1") (pintype "bidirectional"))
      (node (ref "C26") (pin "P$1") (pinfunction "1_P$1") (pintype "bidirectional"))
      (node (ref "C27") (pin "P$1") (pinfunction "1_P$1") (pintype "bidirectional"))
      (node (ref "C28") (pin "P$1") (pinfunction "1_P$1") (pintype "bidirectional"))
      (node (ref "C64") (pin "P$1") (pinfunction "1_P$1") (pintype "bidirectional"))
      (node (ref "C65") (pin "P$1") (pinfunction "1_P$1") (pintype "bidirectional"))
      (node (ref "C66") (pin "P$1") (pinfunction "1_P$1") (pintype "bidirectional"))
      (node (ref "C67") (pin "P$1") (pinfunction "1_P$1") (pintype "bidirectional"))
      (node (ref "C69") (pin "1") (pinfunction "1_1") (pintype "bidirectional"))
      (node (ref "FB6") (pin "P$1") (pinfunction "1_P$1") (pintype "bidirectional"))
      (node (ref "R15") (pin "P$2") (pinfunction "2_P$2") (pintype "bidirectional"))
      (node (ref "R17") (pin "P$2") (pinfunction "2_P$2") (pintype "bidirectional"))
      (node (ref "U1") (pin "16") (pinfunction "VDD33_16") (pintype "bidirectional"))
      (node (ref "U1") (pin "34") (pinfunction "VDD33_34") (pintype "bidirectional"))
      (node (ref "U1") (pin "52") (pinfunction "VDD33_52") (pintype "bidirectional"))
      (node (ref "U1") (pin "63") (pinfunction "VDD33_63") (pintype "bidirectional"))
    )
    (net (code "52") (name "unconnected-(U1A-NC-Pad60)") (class "Default")
      (node (ref "U1") (pin "60") (pinfunction "NC_60") (pintype "bidirectional"))
    )
    (net (code "53") (name "unconnected-(U1B-AUTOENZ{slash}HS_SUSPEND-Pad45)") (class "Default")
      (node (ref "U1") (pin "45") (pinfunction "AUTOENZ/HS_SUSPEND_45") (pintype "bidirectional"))
    )
    (net (code "54") (name "unconnected-(U1B-GRSTZ-Pad50)") (class "Default")
      (node (ref "U1") (pin "50") (pinfunction "GRSTZ_50") (pintype "bidirectional"))
    )
    (net (code "55") (name "unconnected-(U1B-PWRCTL_POL-Pad41)") (class "Default")
      (node (ref "U1") (pin "41") (pinfunction "PWRCTL_POL_41") (pintype "bidirectional"))
    )
    (net (code "56") (name "unconnected-(U1B-SCL{slash}SMBCLK-Pad38)") (class "Default")
      (node (ref "U1") (pin "38") (pinfunction "SCL/SMBCLK_38") (pintype "bidirectional"))
    )
    (net (code "57") (name "unconnected-(U1B-SDA{slash}SMBDAT-Pad37)") (class "Default")
      (node (ref "U1") (pin "37") (pinfunction "SDA/SMBDAT_37") (pintype "bidirectional"))
    )
    (net (code "58") (name "unconnected-(U1B-SMBUSZ{slash}SS_SUSPEND-Pad39)") (class "Default")
      (node (ref "U1") (pin "39") (pinfunction "SMBUSZ/SS_SUSPEND_39") (pintype "bidirectional"))
    )
    (net (code "59") (name "unconnected-(U1B-TEST-Pad49)") (class "Default")
      (node (ref "U1") (pin "49") (pinfunction "TEST_49") (pintype "bidirectional"))
    )
    (net (code "60") (name "unconnected-(U1C-OVERCUR3Z-Pad44)") (class "Default")
      (node (ref "U1") (pin "44") (pinfunction "OVERCUR3Z_44") (pintype "bidirectional"))
    )
    (net (code "61") (name "unconnected-(U1C-OVERCUR4Z-Pad43)") (class "Default")
      (node (ref "U1") (pin "43") (pinfunction "OVERCUR4Z_43") (pintype "bidirectional"))
    )
    (net (code "62") (name "unconnected-(U1C-P3_D_N-Pad18)") (class "Default")
      (node (ref "U1") (pin "18") (pinfunction "P3_D_N_18") (pintype "bidirectional"))
    )
    (net (code "63") (name "unconnected-(U1C-P3_D_P-Pad17)") (class "Default")
      (node (ref "U1") (pin "17") (pinfunction "P3_D_P_17") (pintype "bidirectional"))
    )
    (net (code "64") (name "unconnected-(U1C-P3_SSRX_N-Pad23)") (class "Default")
      (node (ref "U1") (pin "23") (pinfunction "P3_SSRX_N_23") (pintype "bidirectional"))
    )
    (net (code "65") (name "unconnected-(U1C-P3_SSRX_P-Pad22)") (class "Default")
      (node (ref "U1") (pin "22") (pinfunction "P3_SSRX_P_22") (pintype "bidirectional"))
    )
    (net (code "66") (name "unconnected-(U1C-P3_SSTX_N-Pad20)") (class "Default")
      (node (ref "U1") (pin "20") (pinfunction "P3_SSTX_N_20") (pintype "bidirectional"))
    )
    (net (code "67") (name "unconnected-(U1C-P3_SSTX_P-Pad19)") (class "Default")
      (node (ref "U1") (pin "19") (pinfunction "P3_SSTX_P_19") (pintype "bidirectional"))
    )
    (net (code "68") (name "unconnected-(U1C-P4_D_N-Pad25)") (class "Default")
      (node (ref "U1") (pin "25") (pinfunction "P4_D_N_25") (pintype "bidirectional"))
    )
    (net (code "69") (name "unconnected-(U1C-P4_D_P-Pad24)") (class "Default")
      (node (ref "U1") (pin "24") (pinfunction "P4_D_P_24") (pintype "bidirectional"))
    )
    (net (code "70") (name "unconnected-(U1C-P4_SSRX_N-Pad30)") (class "Default")
      (node (ref "U1") (pin "30") (pinfunction "P4_SSRX_N_30") (pintype "bidirectional"))
    )
    (net (code "71") (name "unconnected-(U1C-P4_SSRX_P-Pad29)") (class "Default")
      (node (ref "U1") (pin "29") (pinfunction "P4_SSRX_P_29") (pintype "bidirectional"))
    )
    (net (code "72") (name "unconnected-(U1C-P4_SSTX_N-Pad27)") (class "Default")
      (node (ref "U1") (pin "27") (pinfunction "P4_SSTX_N_27") (pintype "bidirectional"))
    )
    (net (code "73") (name "unconnected-(U1C-P4_SSTX_P-Pad26)") (class "Default")
      (node (ref "U1") (pin "26") (pinfunction "P4_SSTX_P_26") (pintype "bidirectional"))
    )
    (net (code "74") (name "unconnected-(U1C-PWRCTL3{slash}BATEN3-Pad33)") (class "Default")
      (node (ref "U1") (pin "33") (pinfunction "PWRCTL3/BATEN3_33") (pintype "bidirectional"))
    )
    (net (code "75") (name "unconnected-(U1C-PWRCTL4{slash}BATEN4-Pad32)") (class "Default")
      (node (ref "U1") (pin "32") (pinfunction "PWRCTL4/BATEN4_32") (pintype "bidirectional"))
    )
    (net (code "76") (name "unconnected-(U8-NC-Pad17)") (class "Default")
      (node (ref "U8") (pin "17") (pinfunction "NC_17") (pintype "bidirectional"))
    )
    (net (code "77") (name "unconnected-(U8-PG-Pad9)") (class "Default")
      (node (ref "U8") (pin "9") (pinfunction "PG_9") (pintype "bidirectional"))
    )
    (net (code "78") (name "unconnected-(U8-SS-Pad15)") (class "Default")
      (node (ref "U8") (pin "15") (pinfunction "SS_15") (pintype "bidirectional"))
    )
  )
)
